# Piksey_Pico_A1.net
KiCad netlist of a schematic drawn in EAGLE
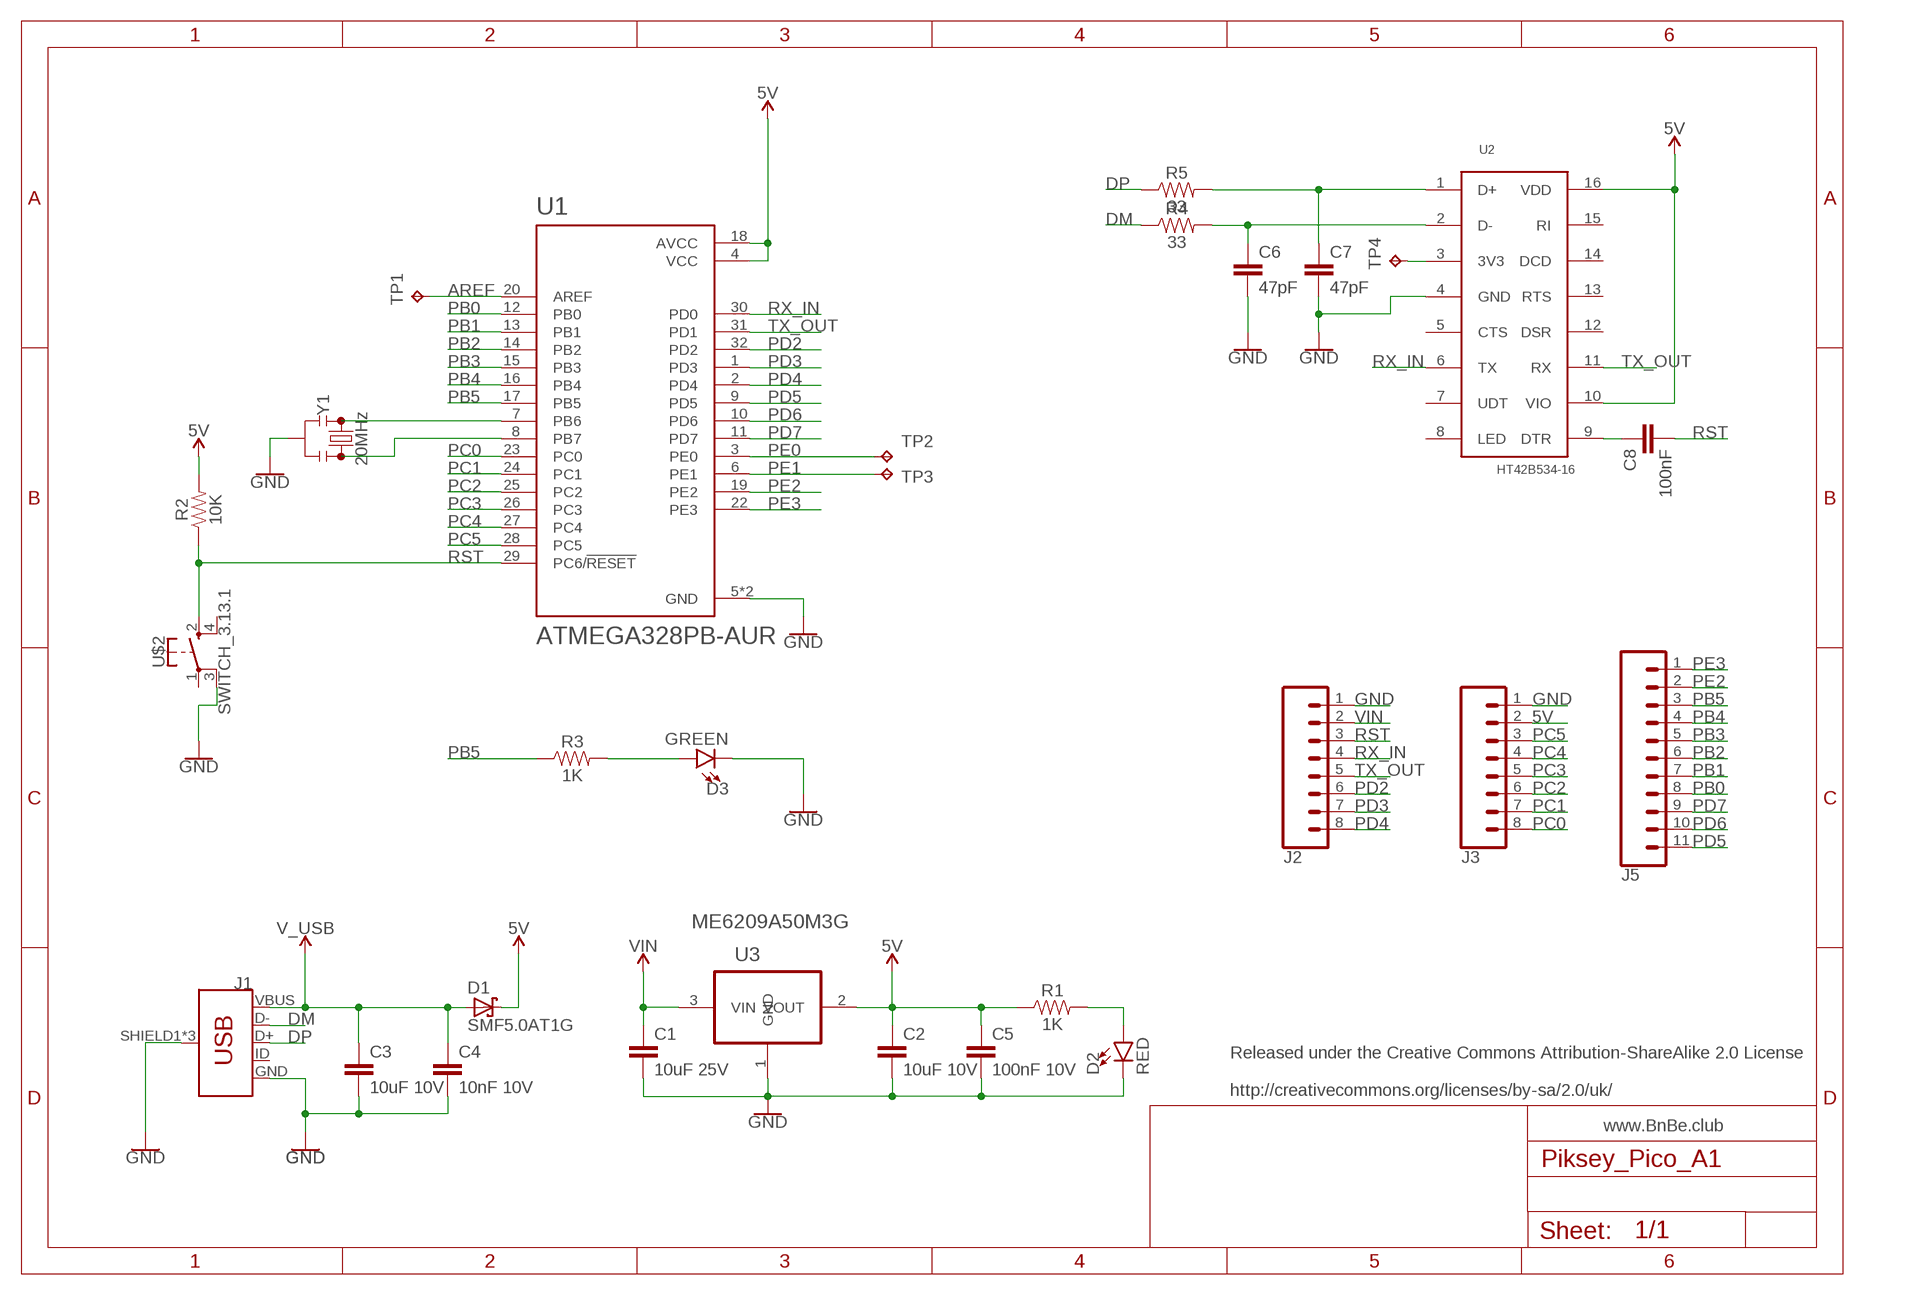
[diagram p0: schematic, sheet 1]

(export (version "E")
  (design (tool "Eeschema 10.0.6"))
  (components
    (comp (ref "C1")
      (value "10uF 25V")
      (footprint "eagle-import:0603")
      (libsource (lib "eagle-import") (part "10UF-0603-6.3V-20%"))
    )
    (comp (ref "C2")
      (value "10uF 10V")
      (footprint "eagle-import:0402")
      (libsource (lib "eagle-import") (part "100PF-0402-50V-5%"))
    )
    (comp (ref "C3")
      (value "10uF 10V")
      (footprint "eagle-import:0402")
      (libsource (lib "eagle-import") (part "100PF-0402-50V-5%"))
    )
    (comp (ref "C4")
      (value "10nF 10V")
      (footprint "eagle-import:0402")
      (libsource (lib "eagle-import") (part "100PF-0402-50V-5%"))
    )
    (comp (ref "C5")
      (value "100nF 10V")
      (footprint "eagle-import:0402")
      (libsource (lib "eagle-import") (part "100PF-0402-50V-5%"))
    )
    (comp (ref "C6")
      (value "47pF")
      (footprint "eagle-import:0402")
      (libsource (lib "eagle-import") (part "100PF-0402-50V-5%"))
    )
    (comp (ref "C7")
      (value "47pF")
      (footprint "eagle-import:0402")
      (libsource (lib "eagle-import") (part "100PF-0402-50V-5%"))
    )
    (comp (ref "C8")
      (value "100nF")
      (footprint "eagle-import:0402")
      (libsource (lib "eagle-import") (part "100PF-0402-50V-5%"))
    )
    (comp (ref "D1")
      (value "SMF5.0AT1G")
      (footprint "eagle-import:SOD123FL")
      (fields (field (name "MF") "Littelfuse"))
      (libsource (lib "eagle-import") (part "SMF5.0AT1G"))
    )
    (comp (ref "D2")
      (value "RED")
      (footprint "eagle-import:LED-0603")
      (libsource (lib "eagle-import") (part "LED0603"))
    )
    (comp (ref "D3")
      (value "GREEN")
      (footprint "eagle-import:LED-0603")
      (libsource (lib "eagle-import") (part "LED0603"))
    )
    (comp (ref "J1")
      (value "USB_MICRO-B_FEMALE-SMT")
      (footprint "eagle-import:USB-B-MICRO-SMD")
      (libsource (lib "eagle-import") (part "USB_MICRO-B_FEMALE-SMT"))
    )
    (comp (ref "J2")
      (value "CONN_08NO_SILK_FEMALE_PTH")
      (footprint "eagle-import:1X08_NO_SILK")
      (libsource (lib "eagle-import") (part "CONN_08NO_SILK_FEMALE_PTH"))
    )
    (comp (ref "J3")
      (value "CONN_08NO_SILK_FEMALE_PTH")
      (footprint "eagle-import:1X08_NO_SILK")
      (libsource (lib "eagle-import") (part "CONN_08NO_SILK_FEMALE_PTH"))
    )
    (comp (ref "J5")
      (value "CONN_11_1.27MM")
      (footprint "eagle-import:1X11-1.27MM")
      (libsource (lib "eagle-import") (part "CONN_11_1.27MM"))
    )
    (comp (ref "R1")
      (value "1K")
      (footprint "eagle-import:0402")
      (libsource (lib "eagle-import") (part "RESISTOR0402"))
    )
    (comp (ref "R2")
      (value "10K")
      (footprint "eagle-import:0402")
      (libsource (lib "eagle-import") (part "RESISTOR0402"))
    )
    (comp (ref "R3")
      (value "1K")
      (footprint "eagle-import:0402")
      (libsource (lib "eagle-import") (part "RESISTOR0402"))
    )
    (comp (ref "R4")
      (value "33")
      (footprint "eagle-import:0402")
      (libsource (lib "eagle-import") (part "RESISTOR0402"))
    )
    (comp (ref "R5")
      (value "33")
      (footprint "eagle-import:0402")
      (libsource (lib "eagle-import") (part "RESISTOR0402"))
    )
    (comp (ref "TP1")
      (value "TPB1,27")
      (footprint "eagle-import:B1,27")
      (libsource (lib "eagle-import") (part "TPB1,27"))
    )
    (comp (ref "TP2")
      (value "TPB1,27")
      (footprint "eagle-import:B1,27")
      (libsource (lib "eagle-import") (part "TPB1,27"))
    )
    (comp (ref "TP3")
      (value "TPB1,27")
      (footprint "eagle-import:B1,27")
      (libsource (lib "eagle-import") (part "TPB1,27"))
    )
    (comp (ref "TP4")
      (value "TPB1,27")
      (footprint "eagle-import:B1,27")
      (libsource (lib "eagle-import") (part "TPB1,27"))
    )
    (comp (ref "U$2")
      (value "SWITCH_3.13.1")
      (footprint "eagle-import:SWITCH_3.1X3.1")
      (libsource (lib "eagle-import") (part "SWITCH_3.13.1"))
    )
    (comp (ref "U1")
      (value "ATMEGA328PB-AUR")
      (footprint "eagle-import:QFP80P900X900X120-32N")
      (fields (field (name "MF") "Microchip"))
      (libsource (lib "eagle-import") (part "ATMEGA328PB-AUR"))
    )
    (comp (ref "U2")
      (value "HT42B534-16")
      (footprint "eagle-import:NSOP-16")
      (libsource (lib "eagle-import") (part "HT42B534-16"))
    )
    (comp (ref "U3")
      (value "ME6209A50M3G")
      (footprint "eagle-import:SOT95P237X112-3N")
      (fields (field (name "MF") "Microchip") (field (name "MP") "MCP1700T-3302E/TT"))
      (libsource (lib "eagle-import") (part "MCP1700T-3302E/TT"))
    )
    (comp (ref "Y1")
      (value "20MHz")
      (footprint "eagle-import:RESONATOR-SMD-3.2X1.3")
      (libsource (lib "eagle-import") (part "RESONATOR-16MHZSMD_3.2X1.3"))
    )
  )
  (nets
    (net (code "1") (name "/AREF") (class "Default")
      (node (ref "TP1") (pin "TP") (pinfunction "TP_TP") (pintype "input"))
      (node (ref "U1") (pin "20") (pinfunction "AREF_20") (pintype "input"))
    )
    (net (code "2") (name "/DM") (class "Default")
      (node (ref "J1") (pin "D-") (pinfunction "D-_D-") (pintype "bidirectional"))
      (node (ref "R4") (pin "1") (pinfunction "1_1") (pintype "passive"))
    )
    (net (code "3") (name "/DP") (class "Default")
      (node (ref "J1") (pin "D+") (pinfunction "D+_D+") (pintype "bidirectional"))
      (node (ref "R5") (pin "1") (pinfunction "1_1") (pintype "passive"))
    )
    (net (code "4") (name "/PB0") (class "Default")
      (node (ref "J5") (pin "8") (pinfunction "8_8") (pintype "passive"))
      (node (ref "U1") (pin "12") (pinfunction "PB0_12") (pintype "bidirectional"))
    )
    (net (code "5") (name "/PB1") (class "Default")
      (node (ref "J5") (pin "7") (pinfunction "7_7") (pintype "passive"))
      (node (ref "U1") (pin "13") (pinfunction "PB1_13") (pintype "bidirectional"))
    )
    (net (code "6") (name "/PB2") (class "Default")
      (node (ref "J5") (pin "6") (pinfunction "6_6") (pintype "passive"))
      (node (ref "U1") (pin "14") (pinfunction "PB2_14") (pintype "bidirectional"))
    )
    (net (code "7") (name "/PB3") (class "Default")
      (node (ref "J5") (pin "5") (pinfunction "5_5") (pintype "passive"))
      (node (ref "U1") (pin "15") (pinfunction "PB3_15") (pintype "bidirectional"))
    )
    (net (code "8") (name "/PB4") (class "Default")
      (node (ref "J5") (pin "4") (pinfunction "4_4") (pintype "passive"))
      (node (ref "U1") (pin "16") (pinfunction "PB4_16") (pintype "bidirectional"))
    )
    (net (code "9") (name "/PB5") (class "Default")
      (node (ref "J5") (pin "3") (pinfunction "3_3") (pintype "passive"))
      (node (ref "R3") (pin "1") (pinfunction "1_1") (pintype "passive"))
      (node (ref "U1") (pin "17") (pinfunction "PB5_17") (pintype "bidirectional"))
    )
    (net (code "10") (name "/PC0") (class "Default")
      (node (ref "J3") (pin "8") (pinfunction "8_8") (pintype "passive"))
      (node (ref "U1") (pin "23") (pinfunction "PC0_23") (pintype "bidirectional"))
    )
    (net (code "11") (name "/PC1") (class "Default")
      (node (ref "J3") (pin "7") (pinfunction "7_7") (pintype "passive"))
      (node (ref "U1") (pin "24") (pinfunction "PC1_24") (pintype "bidirectional"))
    )
    (net (code "12") (name "/PC2") (class "Default")
      (node (ref "J3") (pin "6") (pinfunction "6_6") (pintype "passive"))
      (node (ref "U1") (pin "25") (pinfunction "PC2_25") (pintype "bidirectional"))
    )
    (net (code "13") (name "/PC3") (class "Default")
      (node (ref "J3") (pin "5") (pinfunction "5_5") (pintype "passive"))
      (node (ref "U1") (pin "26") (pinfunction "PC3_26") (pintype "bidirectional"))
    )
    (net (code "14") (name "/PC4") (class "Default")
      (node (ref "J3") (pin "4") (pinfunction "4_4") (pintype "passive"))
      (node (ref "U1") (pin "27") (pinfunction "PC4_27") (pintype "bidirectional"))
    )
    (net (code "15") (name "/PC5") (class "Default")
      (node (ref "J3") (pin "3") (pinfunction "3_3") (pintype "passive"))
      (node (ref "U1") (pin "28") (pinfunction "PC5_28") (pintype "bidirectional"))
    )
    (net (code "16") (name "/PD2") (class "Default")
      (node (ref "J2") (pin "6") (pinfunction "6_6") (pintype "passive"))
      (node (ref "U1") (pin "32") (pinfunction "PD2_32") (pintype "bidirectional"))
    )
    (net (code "17") (name "/PD3") (class "Default")
      (node (ref "J2") (pin "7") (pinfunction "7_7") (pintype "passive"))
      (node (ref "U1") (pin "1") (pinfunction "PD3_1") (pintype "bidirectional"))
    )
    (net (code "18") (name "/PD4") (class "Default")
      (node (ref "J2") (pin "8") (pinfunction "8_8") (pintype "passive"))
      (node (ref "U1") (pin "2") (pinfunction "PD4_2") (pintype "bidirectional"))
    )
    (net (code "19") (name "/PD5") (class "Default")
      (node (ref "J5") (pin "11") (pinfunction "11_11") (pintype "passive"))
      (node (ref "U1") (pin "9") (pinfunction "PD5_9") (pintype "bidirectional"))
    )
    (net (code "20") (name "/PD6") (class "Default")
      (node (ref "J5") (pin "10") (pinfunction "10_10") (pintype "passive"))
      (node (ref "U1") (pin "10") (pinfunction "PD6_10") (pintype "bidirectional"))
    )
    (net (code "21") (name "/PD7") (class "Default")
      (node (ref "J5") (pin "9") (pinfunction "9_9") (pintype "passive"))
      (node (ref "U1") (pin "11") (pinfunction "PD7_11") (pintype "bidirectional"))
    )
    (net (code "22") (name "/PE0") (class "Default")
      (node (ref "TP2") (pin "TP") (pinfunction "TP_TP") (pintype "input"))
      (node (ref "U1") (pin "3") (pinfunction "PE0_3") (pintype "bidirectional"))
    )
    (net (code "23") (name "/PE1") (class "Default")
      (node (ref "TP3") (pin "TP") (pinfunction "TP_TP") (pintype "input"))
      (node (ref "U1") (pin "6") (pinfunction "PE1_6") (pintype "bidirectional"))
    )
    (net (code "24") (name "/PE2") (class "Default")
      (node (ref "J5") (pin "2") (pinfunction "2_2") (pintype "passive"))
      (node (ref "U1") (pin "19") (pinfunction "PE2_19") (pintype "bidirectional"))
    )
    (net (code "25") (name "/PE3") (class "Default")
      (node (ref "J5") (pin "1") (pinfunction "1_1") (pintype "passive"))
      (node (ref "U1") (pin "22") (pinfunction "PE3_22") (pintype "bidirectional"))
    )
    (net (code "26") (name "/RST") (class "Default")
      (node (ref "C8") (pin "2") (pinfunction "2_2") (pintype "passive"))
      (node (ref "J2") (pin "3") (pinfunction "3_3") (pintype "passive"))
      (node (ref "R2") (pin "1") (pinfunction "1_1") (pintype "passive"))
      (node (ref "U$2") (pin "2") (pinfunction "3_2") (pintype "passive"))
      (node (ref "U1") (pin "29") (pinfunction "PC6/~{RESET}_29") (pintype "bidirectional"))
    )
    (net (code "27") (name "/RX_IN") (class "Default")
      (node (ref "J2") (pin "4") (pinfunction "4_4") (pintype "passive"))
      (node (ref "U1") (pin "30") (pinfunction "PD0_30") (pintype "bidirectional"))
      (node (ref "U2") (pin "6") (pinfunction "TX_6") (pintype "bidirectional"))
    )
    (net (code "28") (name "/TX_OUT") (class "Default")
      (node (ref "J2") (pin "5") (pinfunction "5_5") (pintype "passive"))
      (node (ref "U1") (pin "31") (pinfunction "PD1_31") (pintype "bidirectional"))
      (node (ref "U2") (pin "11") (pinfunction "RX_11") (pintype "bidirectional"))
    )
    (net (code "29") (name "5V") (class "Default")
      (node (ref "C2") (pin "1") (pinfunction "1_1") (pintype "passive"))
      (node (ref "C5") (pin "1") (pinfunction "1_1") (pintype "passive"))
      (node (ref "D1") (pin "C") (pinfunction "C_C") (pintype "passive"))
      (node (ref "J3") (pin "2") (pinfunction "2_2") (pintype "passive"))
      (node (ref "R1") (pin "1") (pinfunction "1_1") (pintype "passive"))
      (node (ref "R2") (pin "2") (pinfunction "2_2") (pintype "passive"))
      (node (ref "U1") (pin "18") (pinfunction "AVCC_18") (pintype "power_in"))
      (node (ref "U1") (pin "4") (pinfunction "VCC_4") (pintype "power_in"))
      (node (ref "U2") (pin "10") (pinfunction "VIO_10") (pintype "bidirectional"))
      (node (ref "U2") (pin "16") (pinfunction "VDD_16") (pintype "bidirectional"))
      (node (ref "U3") (pin "2") (pinfunction "VOUT_2") (pintype "output"))
    )
    (net (code "30") (name "GND") (class "Default")
      (node (ref "C1") (pin "2") (pinfunction "2_2") (pintype "passive"))
      (node (ref "C2") (pin "2") (pinfunction "2_2") (pintype "passive"))
      (node (ref "C3") (pin "2") (pinfunction "2_2") (pintype "passive"))
      (node (ref "C4") (pin "2") (pinfunction "2_2") (pintype "passive"))
      (node (ref "C5") (pin "2") (pinfunction "2_2") (pintype "passive"))
      (node (ref "C6") (pin "2") (pinfunction "2_2") (pintype "passive"))
      (node (ref "C7") (pin "2") (pinfunction "2_2") (pintype "passive"))
      (node (ref "D2") (pin "C") (pinfunction "C_C") (pintype "passive"))
      (node (ref "D3") (pin "C") (pinfunction "C_C") (pintype "passive"))
      (node (ref "J1") (pin "GND") (pinfunction "GND_GND") (pintype "power_in"))
      (node (ref "J1") (pin "SHIELD1") (pinfunction "SHIELD_SHIELD1") (pintype "bidirectional"))
      (node (ref "J1") (pin "SHIELD2") (pinfunction "SHIELD_SHIELD2") (pintype "bidirectional"))
      (node (ref "J1") (pin "SHIELD3") (pinfunction "SHIELD_SHIELD3") (pintype "bidirectional"))
      (node (ref "J2") (pin "1") (pinfunction "1_1") (pintype "passive"))
      (node (ref "J3") (pin "1") (pinfunction "1_1") (pintype "passive"))
      (node (ref "U$2") (pin "3") (pinfunction "2_3") (pintype "passive"))
      (node (ref "U1") (pin "21") (pinfunction "GND_21") (pintype "power_in"))
      (node (ref "U1") (pin "5") (pinfunction "GND_5") (pintype "power_in"))
      (node (ref "U2") (pin "4") (pinfunction "GND_4") (pintype "bidirectional"))
      (node (ref "U3") (pin "1") (pinfunction "GND_1") (pintype "passive"))
      (node (ref "Y1") (pin "2") (pinfunction "2_2") (pintype "passive"))
    )
    (net (code "31") (name "Net-(D2-PadA)") (class "Default")
      (node (ref "D2") (pin "A") (pinfunction "A_A") (pintype "passive"))
      (node (ref "R1") (pin "2") (pinfunction "2_2") (pintype "passive"))
    )
    (net (code "32") (name "Net-(D3-PadA)") (class "Default")
      (node (ref "D3") (pin "A") (pinfunction "A_A") (pintype "passive"))
      (node (ref "R3") (pin "2") (pinfunction "2_2") (pintype "passive"))
    )
    (net (code "33") (name "Net-(U1-PB6)") (class "Default")
      (node (ref "U1") (pin "7") (pinfunction "PB6_7") (pintype "bidirectional"))
      (node (ref "Y1") (pin "1") (pinfunction "1_1") (pintype "passive"))
    )
    (net (code "34") (name "Net-(U1-PB7)") (class "Default")
      (node (ref "U1") (pin "8") (pinfunction "PB7_8") (pintype "bidirectional"))
      (node (ref "Y1") (pin "3") (pinfunction "3_3") (pintype "passive"))
    )
    (net (code "35") (name "Net-(U2-3V3)") (class "Default")
      (node (ref "TP4") (pin "TP") (pinfunction "TP_TP") (pintype "input"))
      (node (ref "U2") (pin "3") (pinfunction "3V3_3") (pintype "bidirectional"))
    )
    (net (code "36") (name "Net-(U2-D+)") (class "Default")
      (node (ref "C7") (pin "1") (pinfunction "1_1") (pintype "passive"))
      (node (ref "R5") (pin "2") (pinfunction "2_2") (pintype "passive"))
      (node (ref "U2") (pin "1") (pinfunction "D+_1") (pintype "bidirectional"))
    )
    (net (code "37") (name "Net-(U2-D-)") (class "Default")
      (node (ref "C6") (pin "1") (pinfunction "1_1") (pintype "passive"))
      (node (ref "R4") (pin "2") (pinfunction "2_2") (pintype "passive"))
      (node (ref "U2") (pin "2") (pinfunction "D-_2") (pintype "bidirectional"))
    )
    (net (code "38") (name "Net-(U2-DTR)") (class "Default")
      (node (ref "C8") (pin "1") (pinfunction "1_1") (pintype "passive"))
      (node (ref "U2") (pin "9") (pinfunction "DTR_9") (pintype "bidirectional"))
    )
    (net (code "39") (name "VIN") (class "Default")
      (node (ref "C1") (pin "1") (pinfunction "1_1") (pintype "passive"))
      (node (ref "J2") (pin "2") (pinfunction "2_2") (pintype "passive"))
      (node (ref "U3") (pin "3") (pinfunction "VIN_3") (pintype "input"))
    )
    (net (code "40") (name "V_USB") (class "Default")
      (node (ref "C3") (pin "1") (pinfunction "1_1") (pintype "passive"))
      (node (ref "C4") (pin "1") (pinfunction "1_1") (pintype "passive"))
      (node (ref "D1") (pin "A") (pinfunction "A_A") (pintype "passive"))
      (node (ref "J1") (pin "VBUS") (pinfunction "VBUS_VBUS") (pintype "power_in"))
    )
    (net (code "41") (name "unconnected-(J1-PadID)") (class "Default")
      (node (ref "J1") (pin "ID") (pinfunction "ID_ID") (pintype "bidirectional"))
    )
    (net (code "42") (name "unconnected-(U$2-Pad1)") (class "Default")
      (node (ref "U$2") (pin "1") (pinfunction "1_1") (pintype "passive"))
    )
    (net (code "43") (name "unconnected-(U$2-Pad4)") (class "Default")
      (node (ref "U$2") (pin "4") (pinfunction "4_4") (pintype "passive"))
    )
    (net (code "44") (name "unconnected-(U2-CTS-Pad5)") (class "Default")
      (node (ref "U2") (pin "5") (pinfunction "CTS_5") (pintype "bidirectional"))
    )
    (net (code "45") (name "unconnected-(U2-DCD-Pad14)") (class "Default")
      (node (ref "U2") (pin "14") (pinfunction "DCD_14") (pintype "bidirectional"))
    )
    (net (code "46") (name "unconnected-(U2-DSR-Pad12)") (class "Default")
      (node (ref "U2") (pin "12") (pinfunction "DSR_12") (pintype "bidirectional"))
    )
    (net (code "47") (name "unconnected-(U2-LED-Pad8)") (class "Default")
      (node (ref "U2") (pin "8") (pinfunction "LED_8") (pintype "bidirectional"))
    )
    (net (code "48") (name "unconnected-(U2-RI-Pad15)") (class "Default")
      (node (ref "U2") (pin "15") (pinfunction "RI_15") (pintype "bidirectional"))
    )
    (net (code "49") (name "unconnected-(U2-RTS-Pad13)") (class "Default")
      (node (ref "U2") (pin "13") (pinfunction "RTS_13") (pintype "bidirectional"))
    )
    (net (code "50") (name "unconnected-(U2-UDT-Pad7)") (class "Default")
      (node (ref "U2") (pin "7") (pinfunction "UDT_7") (pintype "bidirectional"))
    )
  )
)
